# Sheet1.net
KiCad netlist of a schematic drawn in Altium Designer
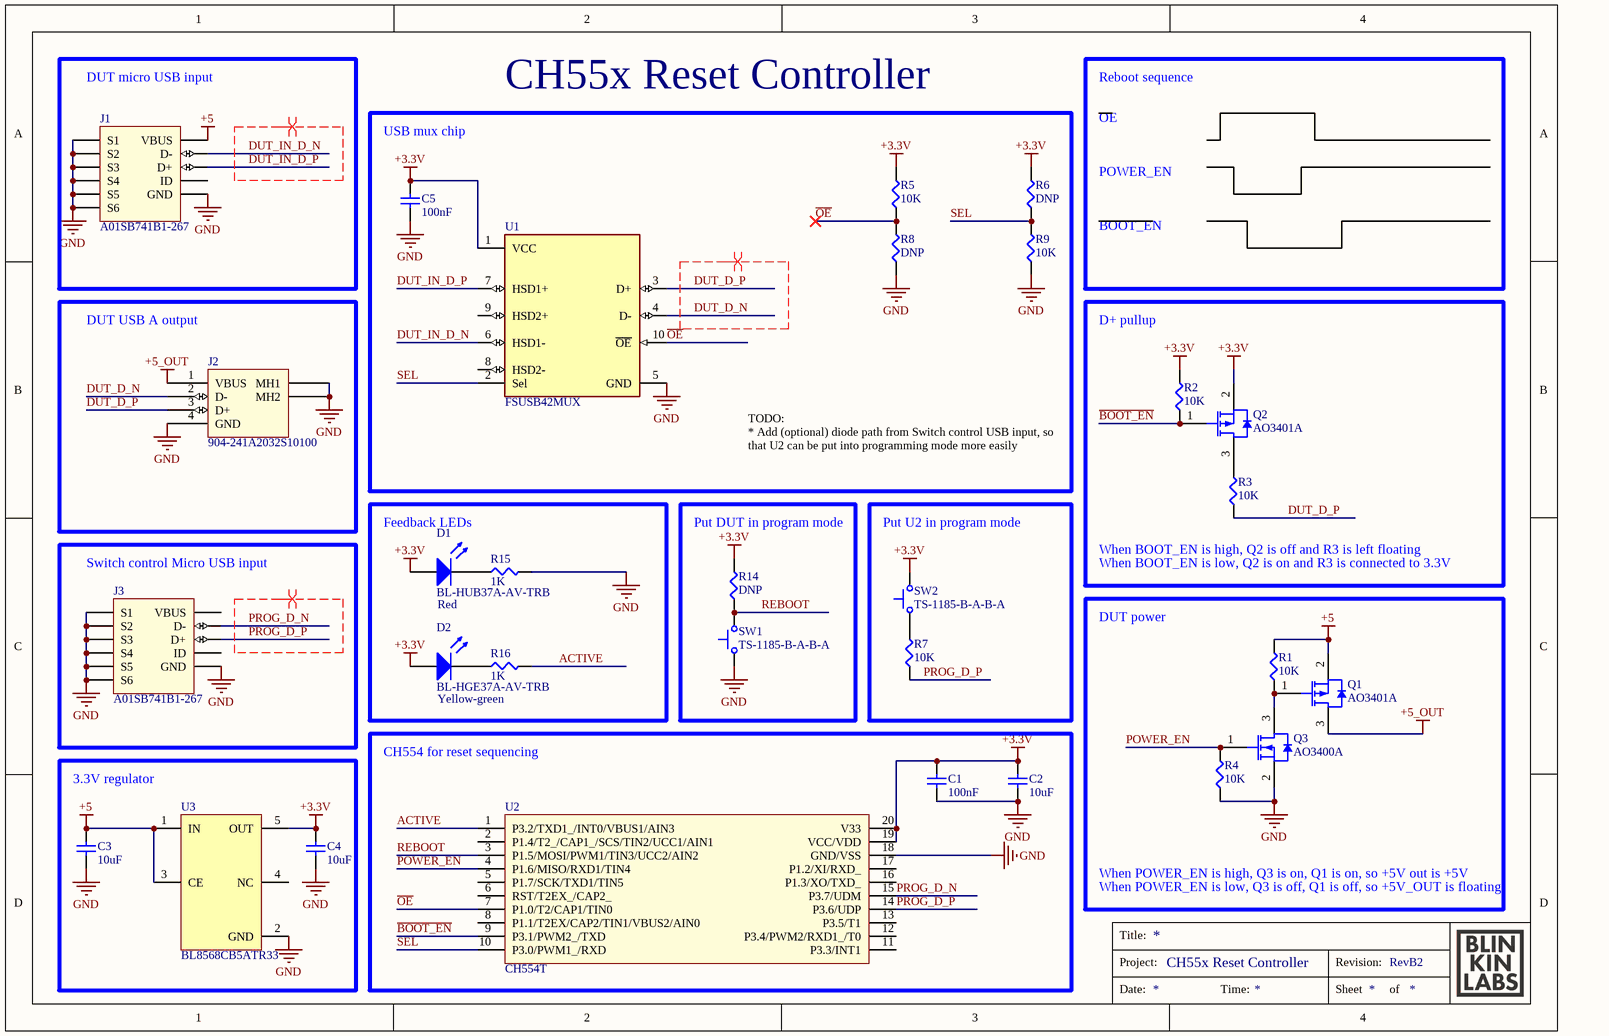
[diagram p0: Sheet1.SchDoc]

(export (version "E")
  (design (tool "Eeschema 10.0.6"))
  (components
    (comp (ref "C1")
      (value "100nF")
      (footprint "CAPC1005X06L")
      (description "CAP SMD 100nF 10% 50V X5R 0402")
      (fields (field (name "TOLERANCE") "10%") (field (name "VOLTAGE") "50V"))
      (libsource (lib "blinkinlabs") (part "CAPACITOR"))
    )
    (comp (ref "C2")
      (value "10uF")
      (footprint "CAPC2012X10L")
      (description "CAP SMD 10uF 10% 25V X5R 0805")
      (fields (field (name "TOLERANCE") "10%") (field (name "VOLTAGE") "25V"))
      (libsource (lib "blinkinlabs") (part "CAPACITOR"))
    )
    (comp (ref "C3")
      (value "10uF")
      (footprint "CAPC2012X10L")
      (description "CAP SMD 10uF 10% 25V X5R 0805")
      (fields (field (name "TOLERANCE") "10%") (field (name "VOLTAGE") "25V"))
      (libsource (lib "blinkinlabs") (part "CAPACITOR"))
    )
    (comp (ref "C4")
      (value "10uF")
      (footprint "CAPC2012X10L")
      (description "CAP SMD 10uF 10% 25V X5R 0805")
      (fields (field (name "TOLERANCE") "10%") (field (name "VOLTAGE") "25V"))
      (libsource (lib "blinkinlabs") (part "CAPACITOR"))
    )
    (comp (ref "C5")
      (value "100nF")
      (footprint "CAPC1005X06L")
      (description "CAP SMD 100nF 10% 50V X5R 0402")
      (fields (field (name "TOLERANCE") "10%") (field (name "VOLTAGE") "50V"))
      (libsource (lib "blinkinlabs") (part "CAPACITOR"))
    )
    (comp (ref "D1")
      (value "BL-HUB37A-AV-TRB")
      (footprint "BL-Hxx37A-AV-TRB")
      (description "LED, 0402, Super Red, 50mcd@20mA, 627~637nm")
      (libsource (lib "blinkinlabs") (part "LED"))
    )
    (comp (ref "D2")
      (value "BL-HGE37A-AV-TRB")
      (footprint "BL-Hxx37A-AV-TRB")
      (description "LED, 0402, Super Yellow Green, 35mcd@20mA, 566~576nm")
      (libsource (lib "blinkinlabs") (part "LED"))
    )
    (comp (ref "J1")
      (value "A01SB741B1-267")
      (footprint "A01SB741B1-267")
      (description "Micro USB B type ??????")
      (libsource (lib "blinkinlabs") (part "A01SB741B1-267"))
    )
    (comp (ref "J2")
      (value "904-241A2032S10100")
      (footprint "C42605")
      (description "USB A connector, SMD, no tabs")
      (libsource (lib "blinkinlabs") (part "C42605"))
    )
    (comp (ref "J3")
      (value "A01SB741B1-267")
      (footprint "A01SB741B1-267")
      (description "Micro USB B type ??????")
      (libsource (lib "blinkinlabs") (part "A01SB741B1-267"))
    )
    (comp (ref "Q1")
      (value "AO3401A")
      (footprint "AO-SOT-23-3L_V")
      (description "MOSFET P-CH 30V 4A SOT23-3L")
      (libsource (lib "blinkinlabs") (part "P_FET"))
    )
    (comp (ref "Q2")
      (value "AO3401A")
      (footprint "AO-SOT-23-3L_V")
      (description "MOSFET P-CH 30V 4A SOT23-3L")
      (libsource (lib "blinkinlabs") (part "P_FET"))
    )
    (comp (ref "Q3")
      (value "AO3400A")
      (footprint "AO-SOT-23-3L_V")
      (description "MOSFET N-CH 30V 5.7A SOT23-3L")
      (libsource (lib "blinkinlabs") (part "N_FET"))
    )
    (comp (ref "R1")
      (value "10K")
      (footprint "ERJ2G(0402)_L")
      (description "RES SMD 10K OHM 5% 1/16W 0402")
      (fields (field (name "TOLERANCE") "5%") (field (name "POWER") "1/16W"))
      (libsource (lib "blinkinlabs") (part "RESISTOR"))
    )
    (comp (ref "R2")
      (value "10K")
      (footprint "ERJ2G(0402)_L")
      (description "RES SMD 10K OHM 5% 1/16W 0402")
      (fields (field (name "TOLERANCE") "5%") (field (name "POWER") "1/16W"))
      (libsource (lib "blinkinlabs") (part "RESISTOR"))
    )
    (comp (ref "R3")
      (value "10K")
      (footprint "ERJ2G(0402)_L")
      (description "RES SMD 10K OHM 5% 1/16W 0402")
      (fields (field (name "TOLERANCE") "5%") (field (name "POWER") "1/16W"))
      (libsource (lib "blinkinlabs") (part "RESISTOR"))
    )
    (comp (ref "R4")
      (value "10K")
      (footprint "ERJ2G(0402)_L")
      (description "RES SMD 10K OHM 5% 1/16W 0402")
      (fields (field (name "TOLERANCE") "5%") (field (name "POWER") "1/16W"))
      (libsource (lib "blinkinlabs") (part "RESISTOR"))
    )
    (comp (ref "R5")
      (value "10K")
      (footprint "ERJ2G(0402)_L")
      (description "RES SMD 10K OHM 5% 1/16W 0402")
      (fields (field (name "TOLERANCE") "5%") (field (name "POWER") "1/16W"))
      (libsource (lib "blinkinlabs") (part "RESISTOR"))
    )
    (comp (ref "R6")
      (value "DNP")
      (footprint "ERJ2G(0402)_L")
      (libsource (lib "blinkinlabs") (part "RESISTOR_DNP"))
    )
    (comp (ref "R7")
      (value "10K")
      (footprint "ERJ2G(0402)_L")
      (description "RES SMD 10K OHM 5% 1/16W 0402")
      (fields (field (name "TOLERANCE") "5%") (field (name "POWER") "1/16W"))
      (libsource (lib "blinkinlabs") (part "RESISTOR"))
    )
    (comp (ref "R8")
      (value "DNP")
      (footprint "ERJ2G(0402)_L")
      (libsource (lib "blinkinlabs") (part "RESISTOR_DNP"))
    )
    (comp (ref "R9")
      (value "10K")
      (footprint "ERJ2G(0402)_L")
      (description "RES SMD 10K OHM 5% 1/16W 0402")
      (fields (field (name "TOLERANCE") "5%") (field (name "POWER") "1/16W"))
      (libsource (lib "blinkinlabs") (part "RESISTOR"))
    )
    (comp (ref "R14")
      (value "DNP")
      (footprint "ERJ2G(0402)_L")
      (libsource (lib "blinkinlabs") (part "RESISTOR_DNP"))
    )
    (comp (ref "R15")
      (value "1K")
      (footprint "ERJ2G(0402)_L")
      (description "RES SMD 1K OHM 5% 1/16W 0402")
      (fields (field (name "TOLERANCE") "5%") (field (name "POWER") "1/16W"))
      (libsource (lib "blinkinlabs") (part "RESISTOR"))
    )
    (comp (ref "R16")
      (value "1K")
      (footprint "ERJ2G(0402)_L")
      (description "RES SMD 1K OHM 5% 1/16W 0402")
      (fields (field (name "TOLERANCE") "5%") (field (name "POWER") "1/16W"))
      (libsource (lib "blinkinlabs") (part "RESISTOR"))
    )
    (comp (ref "SW1")
      (value "TS-1185-B-A-B-A")
      (footprint "TS-1185")
      (description "Tactile switch, SPST, 3x4mm, 50mA 160gf 12V, no mounting pins")
      (libsource (lib "blinkinlabs") (part "TACT_SWITCH_2P"))
    )
    (comp (ref "SW2")
      (value "TS-1185-B-A-B-A")
      (footprint "TS-1185")
      (description "Tactile switch, SPST, 3x4mm, 50mA 160gf 12V, no mounting pins")
      (libsource (lib "blinkinlabs") (part "TACT_SWITCH_2P"))
    )
    (comp (ref "U1")
      (value "FSUSB42MUX")
      (footprint "FP-846AP-MFG")
      (description "USB Switch IC 1 Channel 10-MSOP")
      (libsource (lib "blinkinlabs") (part "FSUSB42MUX"))
    )
    (comp (ref "U2")
      (value "CH554T")
      (footprint "TSOP65P660X110-20N")
      (description "8-bit enhanced USB microcontroller")
      (libsource (lib "blinkinlabs") (part "CH554T"))
    )
    (comp (ref "U3")
      (value "BL8568CB5ATR33")
      (footprint "SOT95P280X130-5N-2")
      (description "500mA High PSRR, Linear Regulator, w. Output Discharge")
      (libsource (lib "blinkinlabs") (part "BL8568CB5ATR33"))
    )
  )
  (nets
    (net (code "1") (name "+3.3V") (class "Default")
      (node (ref "C1") (pin "1") (pinfunction "1_1") (pintype "passive"))
      (node (ref "C2") (pin "1") (pinfunction "1_1") (pintype "passive"))
      (node (ref "C4") (pin "1") (pinfunction "1_1") (pintype "passive"))
      (node (ref "C5") (pin "1") (pinfunction "1_1") (pintype "passive"))
      (node (ref "D1") (pin "1") (pinfunction "1_1") (pintype "passive"))
      (node (ref "D2") (pin "1") (pinfunction "1_1") (pintype "passive"))
      (node (ref "Q2") (pin "2") (pinfunction "SOURCE_2") (pintype "passive"))
      (node (ref "R14") (pin "2") (pinfunction "2_2") (pintype "passive"))
      (node (ref "R2") (pin "2") (pinfunction "2_2") (pintype "passive"))
      (node (ref "R5") (pin "2") (pinfunction "2_2") (pintype "passive"))
      (node (ref "R6") (pin "2") (pinfunction "2_2") (pintype "passive"))
      (node (ref "SW2") (pin "2") (pinfunction "2_2") (pintype "passive"))
      (node (ref "U1") (pin "1") (pinfunction "VCC_1") (pintype "power_in"))
      (node (ref "U2") (pin "19") (pinfunction "VCC/VDD_19") (pintype "power_in"))
      (node (ref "U2") (pin "20") (pinfunction "V33_20") (pintype "power_in"))
      (node (ref "U3") (pin "5") (pinfunction "OUT_5") (pintype "passive"))
    )
    (net (code "2") (name "+5") (class "Default")
      (node (ref "C3") (pin "1") (pinfunction "1_1") (pintype "passive"))
      (node (ref "J1") (pin "VBUS") (pinfunction "VBUS_VBUS") (pintype "power_in"))
      (node (ref "Q1") (pin "2") (pinfunction "SOURCE_2") (pintype "passive"))
      (node (ref "R1") (pin "2") (pinfunction "2_2") (pintype "passive"))
      (node (ref "U3") (pin "1") (pinfunction "IN_1") (pintype "passive"))
      (node (ref "U3") (pin "3") (pinfunction "CE_3") (pintype "passive"))
    )
    (net (code "3") (name "+5_OUT") (class "Default")
      (node (ref "J2") (pin "1") (pinfunction "VBUS_1") (pintype "power_in"))
      (node (ref "Q1") (pin "3") (pinfunction "DRAIN_3") (pintype "passive"))
    )
    (net (code "4") (name "/ACTIVE") (class "Default")
      (node (ref "R16") (pin "2") (pinfunction "2_2") (pintype "passive"))
      (node (ref "U2") (pin "1") (pinfunction "P3.2/TXD1_/INT0/VBUS1/AIN3_1") (pintype "passive"))
    )
    (net (code "5") (name "/DUT_D_N") (class "Default")
      (node (ref "J2") (pin "2") (pinfunction "D-_2") (pintype "bidirectional"))
      (node (ref "U1") (pin "4") (pinfunction "D-_4") (pintype "bidirectional"))
    )
    (net (code "6") (name "/DUT_D_P") (class "Default")
      (node (ref "J2") (pin "3") (pinfunction "D+_3") (pintype "bidirectional"))
      (node (ref "R3") (pin "1") (pinfunction "1_1") (pintype "passive"))
      (node (ref "U1") (pin "3") (pinfunction "D+_3") (pintype "bidirectional"))
    )
    (net (code "7") (name "/DUT_IN_D_N") (class "Default")
      (node (ref "J1") (pin "D-") (pinfunction "D-_D-") (pintype "bidirectional"))
      (node (ref "U1") (pin "6") (pinfunction "HSD1-_6") (pintype "bidirectional"))
    )
    (net (code "8") (name "/DUT_IN_D_P") (class "Default")
      (node (ref "J1") (pin "D+") (pinfunction "D+_D+") (pintype "bidirectional"))
      (node (ref "U1") (pin "7") (pinfunction "HSD1+_7") (pintype "bidirectional"))
    )
    (net (code "9") (name "/POWER_EN") (class "Default")
      (node (ref "Q3") (pin "1") (pinfunction "GATE_1") (pintype "passive"))
      (node (ref "R4") (pin "2") (pinfunction "2_2") (pintype "passive"))
      (node (ref "U2") (pin "4") (pinfunction "P1.6/MISO/RXD1/TIN4_4") (pintype "passive"))
    )
    (net (code "10") (name "/PROG_D_N") (class "Default")
      (node (ref "J3") (pin "D-") (pinfunction "D-_D-") (pintype "bidirectional"))
      (node (ref "U2") (pin "15") (pinfunction "P3.7/UDM_15") (pintype "passive"))
    )
    (net (code "11") (name "/PROG_D_P") (class "Default")
      (node (ref "J3") (pin "D+") (pinfunction "D+_D+") (pintype "bidirectional"))
      (node (ref "R7") (pin "1") (pinfunction "1_1") (pintype "passive"))
      (node (ref "U2") (pin "14") (pinfunction "P3.6/UDP_14") (pintype "passive"))
    )
    (net (code "12") (name "/REBOOT") (class "Default")
      (node (ref "R14") (pin "1") (pinfunction "1_1") (pintype "passive"))
      (node (ref "SW1") (pin "2") (pinfunction "2_2") (pintype "passive"))
      (node (ref "U2") (pin "3") (pinfunction "P1.5/MOSI/PWM1/TIN3/UCC2/AIN2_3") (pintype "passive"))
    )
    (net (code "13") (name "/SEL") (class "Default")
      (node (ref "R6") (pin "1") (pinfunction "1_1") (pintype "passive"))
      (node (ref "R9") (pin "2") (pinfunction "2_2") (pintype "passive"))
      (node (ref "U1") (pin "2") (pinfunction "Sel_2") (pintype "passive"))
      (node (ref "U2") (pin "10") (pinfunction "P3.0/PWM1_/RXD_10") (pintype "passive"))
    )
    (net (code "14") (name "/~{BOOT_EN}") (class "Default")
      (node (ref "Q2") (pin "1") (pinfunction "GATE_1") (pintype "passive"))
      (node (ref "R2") (pin "1") (pinfunction "1_1") (pintype "passive"))
      (node (ref "U2") (pin "9") (pinfunction "P3.1/PWM2_/TXD_9") (pintype "passive"))
    )
    (net (code "15") (name "/~{OE}") (class "Default")
      (node (ref "R5") (pin "1") (pinfunction "1_1") (pintype "passive"))
      (node (ref "R8") (pin "2") (pinfunction "2_2") (pintype "passive"))
      (node (ref "U1") (pin "10") (pinfunction "~{OE}_10") (pintype "input"))
      (node (ref "U2") (pin "7") (pinfunction "P1.0/T2/CAP1/TIN0_7") (pintype "passive"))
    )
    (net (code "16") (name "GND") (class "Default")
      (node (ref "C1") (pin "2") (pinfunction "2_2") (pintype "passive"))
      (node (ref "C2") (pin "2") (pinfunction "2_2") (pintype "passive"))
      (node (ref "C3") (pin "2") (pinfunction "2_2") (pintype "passive"))
      (node (ref "C4") (pin "2") (pinfunction "2_2") (pintype "passive"))
      (node (ref "C5") (pin "2") (pinfunction "2_2") (pintype "passive"))
      (node (ref "J1") (pin "GND") (pinfunction "GND_GND") (pintype "power_in"))
      (node (ref "J1") (pin "S1") (pinfunction "S1_S1") (pintype "passive"))
      (node (ref "J1") (pin "S2") (pinfunction "S2_S2") (pintype "passive"))
      (node (ref "J1") (pin "S3") (pinfunction "S3_S3") (pintype "passive"))
      (node (ref "J1") (pin "S4") (pinfunction "S4_S4") (pintype "passive"))
      (node (ref "J1") (pin "S5") (pinfunction "S5_S5") (pintype "passive"))
      (node (ref "J1") (pin "S6") (pinfunction "S6_S6") (pintype "passive"))
      (node (ref "J2") (pin "4") (pinfunction "GND_4") (pintype "power_in"))
      (node (ref "J2") (pin "5") (pinfunction "MH2_5") (pintype "passive"))
      (node (ref "J2") (pin "6") (pinfunction "MH1_6") (pintype "passive"))
      (node (ref "J3") (pin "GND") (pinfunction "GND_GND") (pintype "power_in"))
      (node (ref "J3") (pin "S1") (pinfunction "S1_S1") (pintype "passive"))
      (node (ref "J3") (pin "S2") (pinfunction "S2_S2") (pintype "passive"))
      (node (ref "J3") (pin "S3") (pinfunction "S3_S3") (pintype "passive"))
      (node (ref "J3") (pin "S4") (pinfunction "S4_S4") (pintype "passive"))
      (node (ref "J3") (pin "S5") (pinfunction "S5_S5") (pintype "passive"))
      (node (ref "J3") (pin "S6") (pinfunction "S6_S6") (pintype "passive"))
      (node (ref "Q3") (pin "2") (pinfunction "SOURCE_2") (pintype "passive"))
      (node (ref "R15") (pin "2") (pinfunction "2_2") (pintype "passive"))
      (node (ref "R4") (pin "1") (pinfunction "1_1") (pintype "passive"))
      (node (ref "R8") (pin "1") (pinfunction "1_1") (pintype "passive"))
      (node (ref "R9") (pin "1") (pinfunction "1_1") (pintype "passive"))
      (node (ref "SW1") (pin "1") (pinfunction "1_1") (pintype "passive"))
      (node (ref "U1") (pin "5") (pinfunction "GND_5") (pintype "power_in"))
      (node (ref "U2") (pin "18") (pinfunction "GND/VSS_18") (pintype "power_in"))
      (node (ref "U3") (pin "2") (pinfunction "GND_2") (pintype "passive"))
    )
    (net (code "17") (name "Net-(D1-Pad2)") (class "Default")
      (node (ref "D1") (pin "2") (pinfunction "2_2") (pintype "passive"))
      (node (ref "R15") (pin "1") (pinfunction "1_1") (pintype "passive"))
    )
    (net (code "18") (name "Net-(D2-Pad2)") (class "Default")
      (node (ref "D2") (pin "2") (pinfunction "2_2") (pintype "passive"))
      (node (ref "R16") (pin "1") (pinfunction "1_1") (pintype "passive"))
    )
    (net (code "19") (name "Net-(Q1-GATE)") (class "Default")
      (node (ref "Q1") (pin "1") (pinfunction "GATE_1") (pintype "passive"))
      (node (ref "Q3") (pin "3") (pinfunction "DRAIN_3") (pintype "passive"))
      (node (ref "R1") (pin "1") (pinfunction "1_1") (pintype "passive"))
    )
    (net (code "20") (name "Net-(Q2-DRAIN)") (class "Default")
      (node (ref "Q2") (pin "3") (pinfunction "DRAIN_3") (pintype "passive"))
      (node (ref "R3") (pin "2") (pinfunction "2_2") (pintype "passive"))
    )
    (net (code "21") (name "Net-(R7-Pad2)") (class "Default")
      (node (ref "R7") (pin "2") (pinfunction "2_2") (pintype "passive"))
      (node (ref "SW2") (pin "1") (pinfunction "1_1") (pintype "passive"))
    )
    (net (code "22") (name "unconnected-(J1-PadID)") (class "Default")
      (node (ref "J1") (pin "ID") (pinfunction "ID_ID") (pintype "passive"))
    )
    (net (code "23") (name "unconnected-(J3-PadID)") (class "Default")
      (node (ref "J3") (pin "ID") (pinfunction "ID_ID") (pintype "passive"))
    )
    (net (code "24") (name "unconnected-(J3-PadVBUS)") (class "Default")
      (node (ref "J3") (pin "VBUS") (pinfunction "VBUS_VBUS") (pintype "power_in"))
    )
    (net (code "25") (name "unconnected-(U1-HSD2+-Pad9)") (class "Default")
      (node (ref "U1") (pin "9") (pinfunction "HSD2+_9") (pintype "bidirectional"))
    )
    (net (code "26") (name "unconnected-(U1-HSD2--Pad8)") (class "Default")
      (node (ref "U1") (pin "8") (pinfunction "HSD2-_8") (pintype "bidirectional"))
    )
    (net (code "27") (name "unconnected-(U2-P1.1{slash}T2EX{slash}CAP2{slash}TIN1{slash}VBUS2{slash}AIN0-Pad8)") (class "Default")
      (node (ref "U2") (pin "8") (pinfunction "P1.1/T2EX/CAP2/TIN1/VBUS2/AIN0_8") (pintype "passive"))
    )
    (net (code "28") (name "unconnected-(U2-P1.2{slash}XI{slash}RXD_-Pad17)") (class "Default")
      (node (ref "U2") (pin "17") (pinfunction "P1.2/XI/RXD__17") (pintype "passive"))
    )
    (net (code "29") (name "unconnected-(U2-P1.3{slash}XO{slash}TXD_-Pad16)") (class "Default")
      (node (ref "U2") (pin "16") (pinfunction "P1.3/XO/TXD__16") (pintype "passive"))
    )
    (net (code "30") (name "unconnected-(U2-P1.4{slash}T2_{slash}CAP1_{slash}SCS{slash}TIN2{slash}UCC1{slash}AIN1-Pad2)") (class "Default")
      (node (ref "U2") (pin "2") (pinfunction "P1.4/T2_/CAP1_/SCS/TIN2/UCC1/AIN1_2") (pintype "passive"))
    )
    (net (code "31") (name "unconnected-(U2-P1.7{slash}SCK{slash}TXD1{slash}TIN5-Pad5)") (class "Default")
      (node (ref "U2") (pin "5") (pinfunction "P1.7/SCK/TXD1/TIN5_5") (pintype "passive"))
    )
    (net (code "32") (name "unconnected-(U2-P3.3{slash}INT1-Pad11)") (class "Default")
      (node (ref "U2") (pin "11") (pinfunction "P3.3/INT1_11") (pintype "passive"))
    )
    (net (code "33") (name "unconnected-(U2-P3.4{slash}PWM2{slash}RXD1_{slash}T0-Pad12)") (class "Default")
      (node (ref "U2") (pin "12") (pinfunction "P3.4/PWM2/RXD1_/T0_12") (pintype "passive"))
    )
    (net (code "34") (name "unconnected-(U2-P3.5{slash}T1-Pad13)") (class "Default")
      (node (ref "U2") (pin "13") (pinfunction "P3.5/T1_13") (pintype "passive"))
    )
    (net (code "35") (name "unconnected-(U2-RST{slash}T2EX_{slash}CAP2_-Pad6)") (class "Default")
      (node (ref "U2") (pin "6") (pinfunction "RST/T2EX_/CAP2__6") (pintype "passive"))
    )
    (net (code "36") (name "unconnected-(U3-NC-Pad4)") (class "Default")
      (node (ref "U3") (pin "4") (pinfunction "NC_4") (pintype "passive"))
    )
  )
)
